# Peripheral.net
KiCad netlist of a schematic drawn in Altium Designer
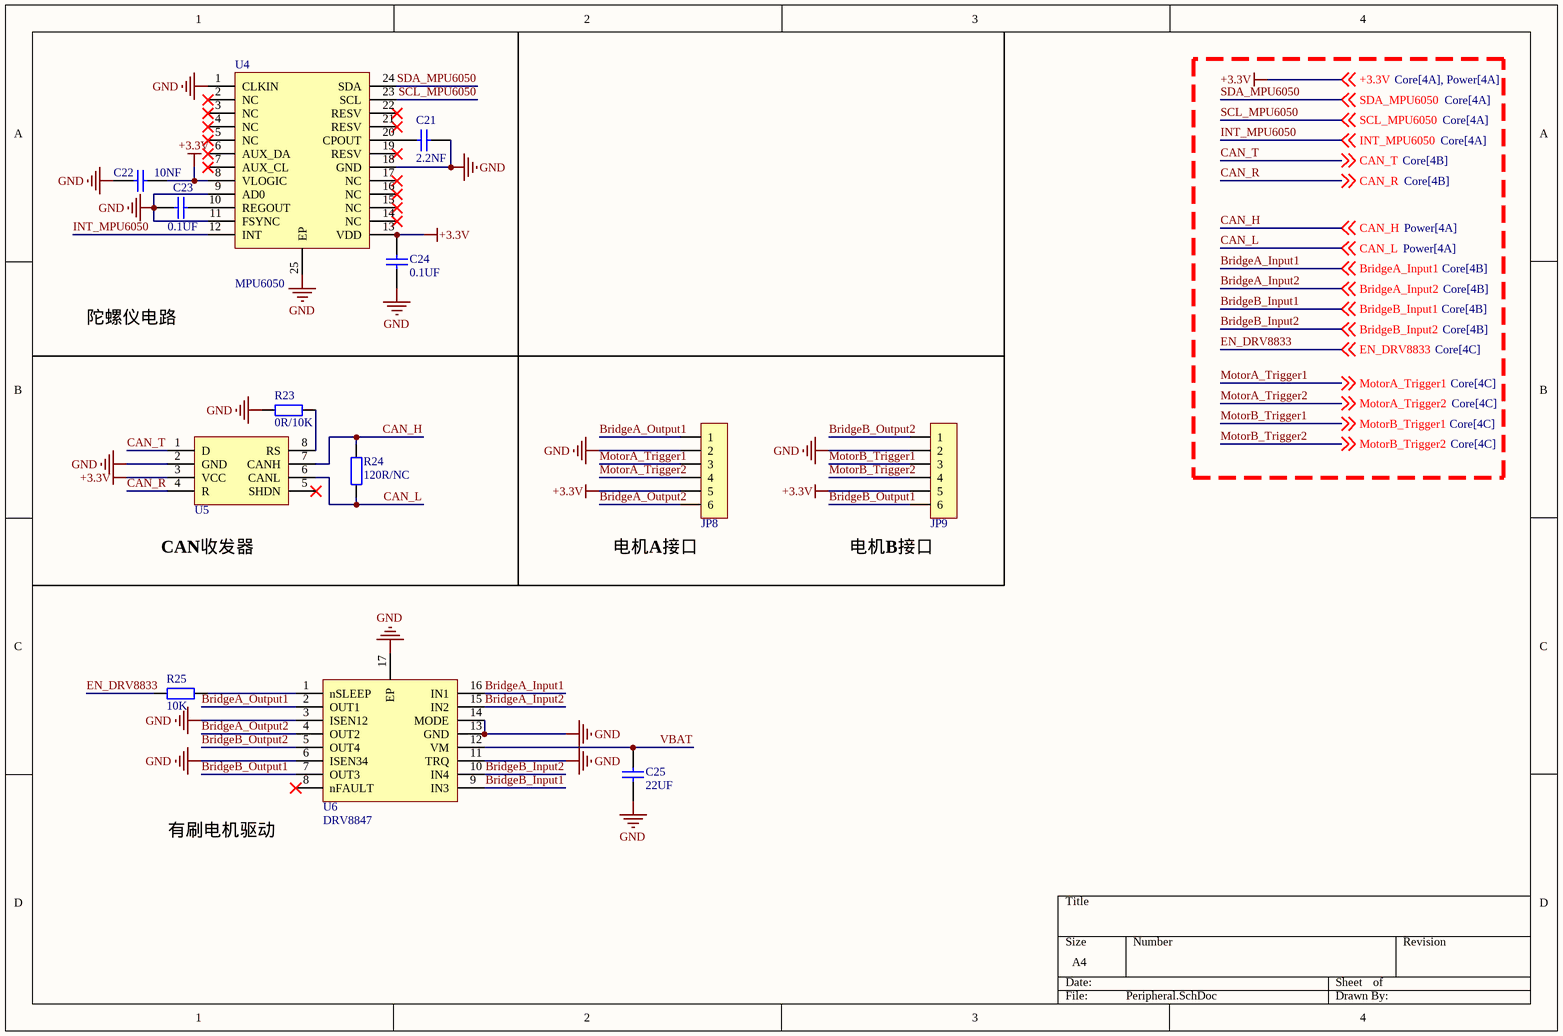
[diagram p0: Peripheral.SchDoc]

(export (version "E")
  (design (tool "Eeschema 10.0.6"))
  (components
    (comp (ref "C21")
      (value "2.2NF")
      (footprint "C0402_NS")
      (description "贴片电容/MLCC电容")
      (libsource (lib "阻容") (part "C"))
    )
    (comp (ref "C22")
      (value "10NF")
      (footprint "C0402_NS")
      (description "贴片电容/MLCC电容")
      (libsource (lib "阻容") (part "C"))
    )
    (comp (ref "C23")
      (value "0.1UF")
      (footprint "C0402_NS")
      (description "贴片电容/MLCC电容")
      (libsource (lib "阻容") (part "C"))
    )
    (comp (ref "C24")
      (value "0.1UF")
      (footprint "C0402_NS")
      (description "贴片电容/MLCC电容")
      (libsource (lib "阻容") (part "C"))
    )
    (comp (ref "C25")
      (value "22UF")
      (footprint "C0805_NS")
      (description "贴片电容/MLCC电容")
      (libsource (lib "阻容") (part "C"))
    )
    (comp (ref "JP8")
      (value "HDR-1X6")
      (footprint "XH2.54-WI-6P")
      (description "6P接插件")
      (libsource (lib "2.54mm连接器") (part "Header 6"))
    )
    (comp (ref "JP9")
      (value "HDR-1X6")
      (footprint "XH2.54-WI-6P")
      (description "6P接插件")
      (libsource (lib "2.54mm连接器") (part "Header 6"))
    )
    (comp (ref "R23")
      (value "0R/10K")
      (footprint "R0402_NS")
      (description "贴片电阻")
      (libsource (lib "阻容") (part "R"))
    )
    (comp (ref "R24")
      (value "120R/NC")
      (footprint "R0402_NS")
      (description "贴片电阻")
      (libsource (lib "阻容") (part "R"))
    )
    (comp (ref "R25")
      (value "10K")
      (footprint "R0402_NS")
      (description "贴片电阻")
      (libsource (lib "阻容") (part "R"))
    )
    (comp (ref "U4")
      (value "MPU6050")
      (footprint "QFN24_L4.0_W4.0_P0.5")
      (libsource (lib "Schlib1") (part "MPU6050"))
    )
    (comp (ref "U5")
      (value "SIT3051")
      (footprint "DFN8_L3.0_W3.0_P0.65")
      (description "CAN收发芯片")
      (fields (field (name "MANUFACTURER") "Texas Instruments"))
      (libsource (lib "协议芯片") (part "SIT3051"))
    )
    (comp (ref "U6")
      (value "DRV8847")
      (footprint "ETSSOP16_L5.0_W4.4_P0.65")
      (description "具有电流调节和独立半桥控制的 18V、2A 双路 H 桥电机驱动器")
      (libsource (lib "电机驱动IC") (part "DRV8847"))
    )
  )
  (nets
    (net (code "1") (name "+3.3V") (class "Default")
      (node (ref "C22") (pin "1") (pinfunction "1_1") (pintype "passive"))
      (node (ref "C24") (pin "2") (pinfunction "2_2") (pintype "passive"))
      (node (ref "JP8") (pin "5") (pinfunction "5_5") (pintype "passive"))
      (node (ref "JP9") (pin "5") (pinfunction "5_5") (pintype "passive"))
      (node (ref "U4") (pin "13") (pinfunction "VDD_13") (pintype "passive"))
      (node (ref "U4") (pin "8") (pinfunction "VLOGIC_8") (pintype "passive"))
      (node (ref "U5") (pin "3") (pinfunction "VCC_3") (pintype "passive"))
    )
    (net (code "2") (name "/BridgeA_Output1") (class "Default")
      (node (ref "JP8") (pin "1") (pinfunction "1_1") (pintype "passive"))
      (node (ref "U6") (pin "2") (pinfunction "OUT1_2") (pintype "passive"))
    )
    (net (code "3") (name "/BridgeA_Output2") (class "Default")
      (node (ref "JP8") (pin "6") (pinfunction "6_6") (pintype "passive"))
      (node (ref "U6") (pin "4") (pinfunction "OUT2_4") (pintype "passive"))
    )
    (net (code "4") (name "/BridgeB_Output1") (class "Default")
      (node (ref "JP9") (pin "6") (pinfunction "6_6") (pintype "passive"))
      (node (ref "U6") (pin "7") (pinfunction "OUT3_7") (pintype "passive"))
    )
    (net (code "5") (name "/BridgeB_Output2") (class "Default")
      (node (ref "JP9") (pin "1") (pinfunction "1_1") (pintype "passive"))
      (node (ref "U6") (pin "5") (pinfunction "OUT4_5") (pintype "passive"))
    )
    (net (code "6") (name "/VBAT") (class "Default")
      (node (ref "C25") (pin "2") (pinfunction "2_2") (pintype "passive"))
      (node (ref "U6") (pin "12") (pinfunction "VM_12") (pintype "passive"))
    )
    (net (code "7") (name "BridgeA_Input1") (class "Default")
      (node (ref "U6") (pin "16") (pinfunction "IN1_16") (pintype "passive"))
    )
    (net (code "8") (name "BridgeA_Input2") (class "Default")
      (node (ref "U6") (pin "15") (pinfunction "IN2_15") (pintype "passive"))
    )
    (net (code "9") (name "BridgeB_Input1") (class "Default")
      (node (ref "U6") (pin "9") (pinfunction "IN3_9") (pintype "passive"))
    )
    (net (code "10") (name "BridgeB_Input2") (class "Default")
      (node (ref "U6") (pin "10") (pinfunction "IN4_10") (pintype "passive"))
    )
    (net (code "11") (name "CAN_H") (class "Default")
      (node (ref "R24") (pin "2") (pinfunction "2_2") (pintype "passive"))
      (node (ref "U5") (pin "7") (pinfunction "CANH_7") (pintype "passive"))
    )
    (net (code "12") (name "CAN_L") (class "Default")
      (node (ref "R24") (pin "1") (pinfunction "1_1") (pintype "passive"))
      (node (ref "U5") (pin "6") (pinfunction "CANL_6") (pintype "passive"))
    )
    (net (code "13") (name "CAN_R") (class "Default")
      (node (ref "U5") (pin "4") (pinfunction "R_4") (pintype "passive"))
    )
    (net (code "14") (name "CAN_T") (class "Default")
      (node (ref "U5") (pin "1") (pinfunction "D_1") (pintype "passive"))
    )
    (net (code "15") (name "EN_DRV8833") (class "Default")
      (node (ref "R25") (pin "1") (pinfunction "1_1") (pintype "passive"))
    )
    (net (code "16") (name "GND") (class "Default")
      (node (ref "C21") (pin "2") (pinfunction "2_2") (pintype "passive"))
      (node (ref "C22") (pin "2") (pinfunction "2_2") (pintype "passive"))
      (node (ref "C23") (pin "2") (pinfunction "2_2") (pintype "passive"))
      (node (ref "C24") (pin "1") (pinfunction "1_1") (pintype "passive"))
      (node (ref "C25") (pin "1") (pinfunction "1_1") (pintype "passive"))
      (node (ref "JP8") (pin "2") (pinfunction "2_2") (pintype "passive"))
      (node (ref "JP9") (pin "2") (pinfunction "2_2") (pintype "passive"))
      (node (ref "R23") (pin "2") (pinfunction "2_2") (pintype "passive"))
      (node (ref "U4") (pin "1") (pinfunction "CLKIN_1") (pintype "passive"))
      (node (ref "U4") (pin "11") (pinfunction "FSYNC_11") (pintype "passive"))
      (node (ref "U4") (pin "18") (pinfunction "GND_18") (pintype "passive"))
      (node (ref "U4") (pin "25") (pinfunction "EP_25") (pintype "passive"))
      (node (ref "U4") (pin "9") (pinfunction "AD0_9") (pintype "passive"))
      (node (ref "U5") (pin "2") (pinfunction "GND_2") (pintype "passive"))
      (node (ref "U6") (pin "11") (pinfunction "TRQ_11") (pintype "passive"))
      (node (ref "U6") (pin "13") (pinfunction "GND_13") (pintype "passive"))
      (node (ref "U6") (pin "14") (pinfunction "MODE_14") (pintype "passive"))
      (node (ref "U6") (pin "17") (pinfunction "EP_17") (pintype "passive"))
      (node (ref "U6") (pin "3") (pinfunction "ISEN12_3") (pintype "passive"))
      (node (ref "U6") (pin "6") (pinfunction "ISEN34_6") (pintype "passive"))
    )
    (net (code "17") (name "INT_MPU6050") (class "Default")
      (node (ref "U4") (pin "12") (pinfunction "INT_12") (pintype "passive"))
    )
    (net (code "18") (name "MotorA_Trigger1") (class "Default")
      (node (ref "JP8") (pin "3") (pinfunction "3_3") (pintype "passive"))
    )
    (net (code "19") (name "MotorA_Trigger2") (class "Default")
      (node (ref "JP8") (pin "4") (pinfunction "4_4") (pintype "passive"))
    )
    (net (code "20") (name "MotorB_Trigger1") (class "Default")
      (node (ref "JP9") (pin "3") (pinfunction "3_3") (pintype "passive"))
    )
    (net (code "21") (name "MotorB_Trigger2") (class "Default")
      (node (ref "JP9") (pin "4") (pinfunction "4_4") (pintype "passive"))
    )
    (net (code "22") (name "Net-(U4-CPOUT)") (class "Default")
      (node (ref "C21") (pin "1") (pinfunction "1_1") (pintype "passive"))
      (node (ref "U4") (pin "20") (pinfunction "CPOUT_20") (pintype "passive"))
    )
    (net (code "23") (name "Net-(U4-REGOUT)") (class "Default")
      (node (ref "C23") (pin "1") (pinfunction "1_1") (pintype "passive"))
      (node (ref "U4") (pin "10") (pinfunction "REGOUT_10") (pintype "passive"))
    )
    (net (code "24") (name "Net-(U5-RS)") (class "Default")
      (node (ref "R23") (pin "1") (pinfunction "1_1") (pintype "passive"))
      (node (ref "U5") (pin "8") (pinfunction "RS_8") (pintype "passive"))
    )
    (net (code "25") (name "Net-(U6-nSLEEP)") (class "Default")
      (node (ref "R25") (pin "2") (pinfunction "2_2") (pintype "passive"))
      (node (ref "U6") (pin "1") (pinfunction "nSLEEP_1") (pintype "passive"))
    )
    (net (code "26") (name "SCL_MPU6050") (class "Default")
      (node (ref "U4") (pin "23") (pinfunction "SCL_23") (pintype "passive"))
    )
    (net (code "27") (name "SDA_MPU6050") (class "Default")
      (node (ref "U4") (pin "24") (pinfunction "SDA_24") (pintype "passive"))
    )
    (net (code "28") (name "unconnected-(U4-AUX_CL-Pad7)") (class "Default")
      (node (ref "U4") (pin "7") (pinfunction "AUX_CL_7") (pintype "passive+no_connect"))
    )
    (net (code "29") (name "unconnected-(U4-AUX_DA-Pad6)") (class "Default")
      (node (ref "U4") (pin "6") (pinfunction "AUX_DA_6") (pintype "passive+no_connect"))
    )
    (net (code "30") (name "unconnected-(U4-NC-Pad2)") (class "Default")
      (node (ref "U4") (pin "2") (pinfunction "NC_2") (pintype "passive+no_connect"))
    )
    (net (code "31") (name "unconnected-(U4-NC-Pad3)") (class "Default")
      (node (ref "U4") (pin "3") (pinfunction "NC_3") (pintype "passive+no_connect"))
    )
    (net (code "32") (name "unconnected-(U4-NC-Pad4)") (class "Default")
      (node (ref "U4") (pin "4") (pinfunction "NC_4") (pintype "passive+no_connect"))
    )
    (net (code "33") (name "unconnected-(U4-NC-Pad5)") (class "Default")
      (node (ref "U4") (pin "5") (pinfunction "NC_5") (pintype "passive+no_connect"))
    )
    (net (code "34") (name "unconnected-(U4-NC-Pad14)") (class "Default")
      (node (ref "U4") (pin "14") (pinfunction "NC_14") (pintype "passive+no_connect"))
    )
    (net (code "35") (name "unconnected-(U4-NC-Pad15)") (class "Default")
      (node (ref "U4") (pin "15") (pinfunction "NC_15") (pintype "passive+no_connect"))
    )
    (net (code "36") (name "unconnected-(U4-NC-Pad16)") (class "Default")
      (node (ref "U4") (pin "16") (pinfunction "NC_16") (pintype "passive+no_connect"))
    )
    (net (code "37") (name "unconnected-(U4-NC-Pad17)") (class "Default")
      (node (ref "U4") (pin "17") (pinfunction "NC_17") (pintype "passive+no_connect"))
    )
    (net (code "38") (name "unconnected-(U4-RESV-Pad19)") (class "Default")
      (node (ref "U4") (pin "19") (pinfunction "RESV_19") (pintype "passive+no_connect"))
    )
    (net (code "39") (name "unconnected-(U4-RESV-Pad21)") (class "Default")
      (node (ref "U4") (pin "21") (pinfunction "RESV_21") (pintype "passive+no_connect"))
    )
    (net (code "40") (name "unconnected-(U4-RESV-Pad22)") (class "Default")
      (node (ref "U4") (pin "22") (pinfunction "RESV_22") (pintype "passive+no_connect"))
    )
    (net (code "41") (name "unconnected-(U5-SHDN-Pad5)") (class "Default")
      (node (ref "U5") (pin "5") (pinfunction "SHDN_5") (pintype "passive+no_connect"))
    )
    (net (code "42") (name "unconnected-(U6-nFAULT-Pad8)") (class "Default")
      (node (ref "U6") (pin "8") (pinfunction "nFAULT_8") (pintype "passive+no_connect"))
    )
  )
)
